# Motor-X.net
KiCad netlist of a schematic drawn in Altium Designer
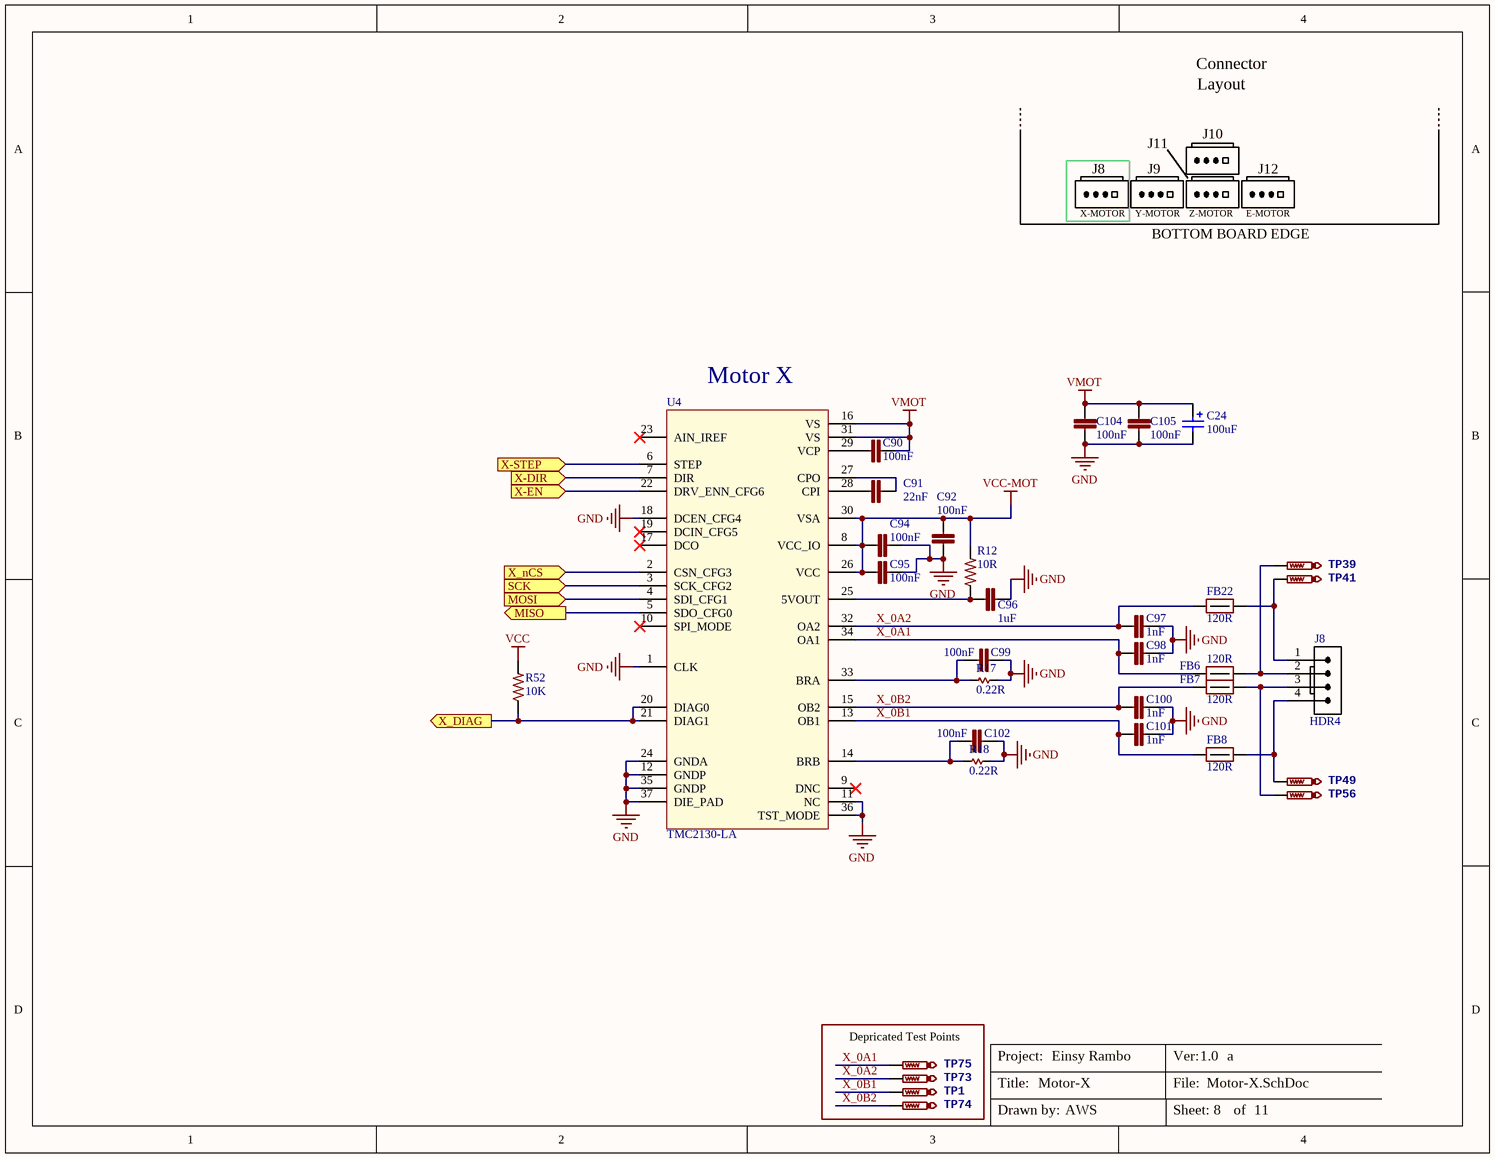
[diagram p0: Motor-X.SchDoc]

(export (version "E")
  (design (tool "Eeschema 10.0.6"))
  (components
    (comp (ref "C24")
      (value "100uF")
      (footprint "CAP-ELEC-063063077")
      (description "CAP ALUM 100UF 35V 20% SMD")
      (fields (field (name "MANUFACTURER") "Nichicon") (field (name "TOLERANCE") "+/- 20%"))
      (libsource (lib "3Delight") (part "UWT1V101MCL1GS"))
    )
    (comp (ref "C90")
      (value "100nF")
      (footprint "C0603")
      (description "CAP CER 0603 100nF 50V 10% X7R")
      (fields (field (name "MANUFACTURER") "Kemet") (field (name "TOLERANCE") "+/- 10%"))
      (libsource (lib "") (part "C0603C104K5RACTU_2"))
    )
    (comp (ref "C91")
      (value "22nF")
      (footprint "C0402")
      (description "CAP CER 0402 22nF ±10% 50V X7R")
      (fields (field (name "MANUFACTURER") "YAGEO") (field (name "TOLERANCE") "+/- 10%"))
      (libsource (lib "3Delight") (part "GCM155R71H223KA55D"))
    )
    (comp (ref "C92")
      (value "100nF")
      (footprint "C0402")
      (description "CAP CER 0402 100nF 16V 10% X7R")
      (fields (field (name "MANUFACTURER") "Murata") (field (name "TOLERANCE") "+/- 10%"))
      (libsource (lib "") (part "GRM155R71C104KA88D_1"))
    )
    (comp (ref "C94")
      (value "100nF")
      (footprint "C0402")
      (description "CAP CER 0402 100nF 16V 10% X7R")
      (fields (field (name "MANUFACTURER") "Murata") (field (name "TOLERANCE") "+/- 10%"))
      (libsource (lib "3Delight") (part "GRM155R71C104KA88D"))
    )
    (comp (ref "C95")
      (value "100nF")
      (footprint "C0402")
      (description "CAP CER 0402 100nF 16V 10% X7R")
      (fields (field (name "MANUFACTURER") "Murata") (field (name "TOLERANCE") "+/- 10%"))
      (libsource (lib "3Delight") (part "GRM155R71C104KA88D"))
    )
    (comp (ref "C96")
      (value "1uF")
      (footprint "C0402")
      (description "CAP CER 0402 1uF 6.3V 10% X5R")
      (fields (field (name "MANUFACTURER") "Murata") (field (name "TOLERANCE") "+/- 10%"))
      (libsource (lib "3Delight") (part "GRM155R60J105KE19D"))
    )
    (comp (ref "C97")
      (value "1nF")
      (footprint "C0603")
      (description "CAP CER 0603  1nF 50v 10% X7R")
      (fields (field (name "MANUFACTURER") "Kemet") (field (name "TOLERANCE") "+/- 10%"))
      (libsource (lib "3Delight") (part "C0603C102K5RACTU"))
    )
    (comp (ref "C98")
      (value "1nF")
      (footprint "C0603")
      (description "CAP CER 0603  1nF 50v 10% X7R")
      (fields (field (name "MANUFACTURER") "Kemet") (field (name "TOLERANCE") "+/- 10%"))
      (libsource (lib "3Delight") (part "C0603C102K5RACTU"))
    )
    (comp (ref "C99")
      (value "100nF")
      (footprint "C0603")
      (description "CAP CER 0603 100nF 50V 10% X7R")
      (fields (field (name "MANUFACTURER") "Kemet") (field (name "TOLERANCE") "+/- 10%"))
      (libsource (lib "") (part "C0603C104K5RACTU_1"))
    )
    (comp (ref "C100")
      (value "1nF")
      (footprint "C0603")
      (description "CAP CER 0603  1nF 50v 10% X7R")
      (fields (field (name "MANUFACTURER") "Kemet") (field (name "TOLERANCE") "+/- 10%"))
      (libsource (lib "3Delight") (part "C0603C102K5RACTU"))
    )
    (comp (ref "C101")
      (value "1nF")
      (footprint "C0603")
      (description "CAP CER 0603  1nF 50v 10% X7R")
      (fields (field (name "MANUFACTURER") "Kemet") (field (name "TOLERANCE") "+/- 10%"))
      (libsource (lib "3Delight") (part "C0603C102K5RACTU"))
    )
    (comp (ref "C102")
      (value "100nF")
      (footprint "C0603")
      (description "CAP CER 0603 100nF 50V 10% X7R")
      (fields (field (name "MANUFACTURER") "Kemet") (field (name "TOLERANCE") "+/- 10%"))
      (libsource (lib "") (part "C0603C104K5RACTU_1"))
    )
    (comp (ref "C104")
      (value "100nF")
      (footprint "C0603")
      (description "CAP CER 0603 100nF 50V 10% X7R")
      (fields (field (name "MANUFACTURER") "Kemet") (field (name "TOLERANCE") "+/- 10%"))
      (libsource (lib "3Delight") (part "C0603C104K5RACTU"))
    )
    (comp (ref "C105")
      (value "100nF")
      (footprint "C0603")
      (description "CAP CER 0603 100nF 50V 10% X7R")
      (fields (field (name "MANUFACTURER") "Kemet") (field (name "TOLERANCE") "+/- 10%"))
      (libsource (lib "3Delight") (part "C0603C104K5RACTU"))
    )
    (comp (ref "FB6")
      (value "120R")
      (footprint "FB0603")
      (description "FERRITE BEAD 120 OHM 0603 1LN")
      (fields (field (name "MANUFACTURER") "Samsung") (field (name "PART") "FERRITE 120R 3A 0603"))
      (libsource (lib "Inductors") (part "FERRITE 120R 3A 0603"))
    )
    (comp (ref "FB7")
      (value "120R")
      (footprint "FB0603")
      (description "FERRITE BEAD 120 OHM 0603 1LN")
      (fields (field (name "MANUFACTURER") "Samsung") (field (name "PART") "FERRITE 120R 3A 0603"))
      (libsource (lib "Inductors") (part "FERRITE 120R 3A 0603"))
    )
    (comp (ref "FB8")
      (value "120R")
      (footprint "FB0603")
      (description "FERRITE BEAD 120 OHM 0603 1LN")
      (fields (field (name "MANUFACTURER") "Samsung") (field (name "PART") "FERRITE 120R 3A 0603"))
      (libsource (lib "Inductors") (part "FERRITE 120R 3A 0603"))
    )
    (comp (ref "FB22")
      (value "120R")
      (footprint "FB0603")
      (description "FERRITE BEAD 120 OHM 0603 1LN")
      (fields (field (name "MANUFACTURER") "Samsung") (field (name "PART") "FERRITE 120R 3A 0603"))
      (libsource (lib "Inductors") (part "FERRITE 120R 3A 0603"))
    )
    (comp (ref "J8")
      (value "HDR4")
      (footprint "4POL254")
      (description "Molex 4 Pin Clip Connector")
      (fields (field (name "MANUFACTURER") "Molex") (field (name "PART") "4 Pin Conn"))
      (libsource (lib "3Delight") (part "CONN 4PIN 0.1{dblquote} VERT SHRD LOCK ALT"))
    )
    (comp (ref "R12")
      (value "10R")
      (footprint "R0402")
      (description "RES SMD 10 OHM 1% 1/16W 0402")
      (fields (field (name "MANUFACTURER") "Yageo") (field (name "TOLERANCE") "+/- 1%"))
      (libsource (lib "3Delight") (part "RC0402FR-0710RL"))
    )
    (comp (ref "R17")
      (value "0.22R")
      (footprint "R1206")
      (description "RES SMD 0.22 OHM 1% 1/3W 1206")
      (fields (field (name "MANUFACTURER") "Panasonic") (field (name "TOLERANCE") "+/- 1%"))
      (libsource (lib "Resistors") (part "0.22R 1% 1206"))
    )
    (comp (ref "R18")
      (value "0.22R")
      (footprint "R1206")
      (description "RES SMD 0.22 OHM 1% 1/3W 1206")
      (fields (field (name "MANUFACTURER") "Panasonic") (field (name "TOLERANCE") "+/- 1%"))
      (libsource (lib "Resistors") (part "0.22R 1% 1206"))
    )
    (comp (ref "R52")
      (value "10K")
      (footprint "R0402")
      (description "RES SMD 10K OHM 1% 1/16W 0402")
      (fields (field (name "MANUFACTURER") "Yageo") (field (name "PART") "10k 1% 0402"))
      (libsource (lib "3Delight") (part "RC0402FR-0710KP"))
    )
    (comp (ref "TP1")
      (value "TestPoint")
      (footprint "TP1-27")
      (description "Test Point")
      (libsource (lib "3Delight") (part "TestPoint"))
    )
    (comp (ref "TP39")
      (value "TestPoint")
      (footprint "TP1-27")
      (description "Test Point")
      (libsource (lib "3Delight") (part "TestPoint"))
    )
    (comp (ref "TP41")
      (value "TestPoint")
      (footprint "TP1-27")
      (description "Test Point")
      (libsource (lib "3Delight") (part "TestPoint"))
    )
    (comp (ref "TP49")
      (value "TestPoint")
      (footprint "TP1-27")
      (description "Test Point")
      (libsource (lib "3Delight") (part "TestPoint"))
    )
    (comp (ref "TP56")
      (value "TestPoint")
      (footprint "TP1-27")
      (description "Test Point")
      (libsource (lib "3Delight") (part "TestPoint"))
    )
    (comp (ref "TP73")
      (value "TestPoint")
      (footprint "TP1-27")
      (description "Test Point")
      (libsource (lib "3Delight") (part "TestPoint"))
    )
    (comp (ref "TP74")
      (value "TestPoint")
      (footprint "TP1-27")
      (description "Test Point")
      (libsource (lib "3Delight") (part "TestPoint"))
    )
    (comp (ref "TP75")
      (value "TestPoint")
      (footprint "TP1-27")
      (description "Test Point")
      (libsource (lib "3Delight") (part "TestPoint"))
    )
    (comp (ref "U4")
      (value "TMC2130-LA")
      (footprint "QFN36-50P500X600X900_HS-37N")
      (description "IC STEPPER MOTOR DVR SPI 36QFN")
      (fields (field (name "MANUFACTURER") "Trinamic") (field (name "PART") "TMC2130"))
      (libsource (lib "3Delight") (part "TMC2130-LA-T"))
    )
  )
  (nets
    (net (code "1") (name "/MISO") (class "Default")
      (node (ref "U4") (pin "5") (pinfunction "SDO_CFG0_5") (pintype "passive"))
    )
    (net (code "2") (name "/MOSI") (class "Default")
      (node (ref "U4") (pin "4") (pinfunction "SDI_CFG1_4") (pintype "passive"))
    )
    (net (code "3") (name "/SCK") (class "Default")
      (node (ref "U4") (pin "3") (pinfunction "SCK_CFG2_3") (pintype "passive"))
    )
    (net (code "4") (name "/X-DIR") (class "Default")
      (node (ref "U4") (pin "7") (pinfunction "DIR_7") (pintype "passive"))
    )
    (net (code "5") (name "/X-EN") (class "Default")
      (node (ref "U4") (pin "22") (pinfunction "DRV_ENN_CFG6_22") (pintype "passive"))
    )
    (net (code "6") (name "/X-STEP") (class "Default")
      (node (ref "U4") (pin "6") (pinfunction "STEP_6") (pintype "passive"))
    )
    (net (code "7") (name "/X_0A1") (class "Default")
      (node (ref "C98") (pin "1") (pinfunction "1_1") (pintype "passive"))
      (node (ref "FB6") (pin "1") (pinfunction "1_1") (pintype "passive"))
      (node (ref "TP75") (pin "TP") (pinfunction "TP_TP") (pintype "passive"))
      (node (ref "U4") (pin "34") (pinfunction "OA1_34") (pintype "passive"))
    )
    (net (code "8") (name "/X_0A2") (class "Default")
      (node (ref "C97") (pin "1") (pinfunction "1_1") (pintype "passive"))
      (node (ref "FB22") (pin "1") (pinfunction "1_1") (pintype "passive"))
      (node (ref "TP73") (pin "TP") (pinfunction "TP_TP") (pintype "passive"))
      (node (ref "U4") (pin "32") (pinfunction "OA2_32") (pintype "passive"))
    )
    (net (code "9") (name "/X_0B1") (class "Default")
      (node (ref "C101") (pin "1") (pinfunction "1_1") (pintype "passive"))
      (node (ref "FB8") (pin "1") (pinfunction "1_1") (pintype "passive"))
      (node (ref "TP1") (pin "TP") (pinfunction "TP_TP") (pintype "passive"))
      (node (ref "U4") (pin "13") (pinfunction "OB1_13") (pintype "passive"))
    )
    (net (code "10") (name "/X_0B2") (class "Default")
      (node (ref "C100") (pin "1") (pinfunction "1_1") (pintype "passive"))
      (node (ref "FB7") (pin "1") (pinfunction "1_1") (pintype "passive"))
      (node (ref "TP74") (pin "TP") (pinfunction "TP_TP") (pintype "passive"))
      (node (ref "U4") (pin "15") (pinfunction "OB2_15") (pintype "passive"))
    )
    (net (code "11") (name "/X_DIAG") (class "Default")
      (node (ref "R52") (pin "1") (pinfunction "1_1") (pintype "passive"))
      (node (ref "U4") (pin "20") (pinfunction "DIAG0_20") (pintype "passive"))
      (node (ref "U4") (pin "21") (pinfunction "DIAG1_21") (pintype "passive"))
    )
    (net (code "12") (name "/X_nCS") (class "Default")
      (node (ref "U4") (pin "2") (pinfunction "CSN_CFG3_2") (pintype "passive"))
    )
    (net (code "13") (name "GND") (class "Default")
      (node (ref "C100") (pin "2") (pinfunction "2_2") (pintype "passive"))
      (node (ref "C101") (pin "2") (pinfunction "2_2") (pintype "passive"))
      (node (ref "C102") (pin "1") (pinfunction "1_1") (pintype "passive"))
      (node (ref "C104") (pin "1") (pinfunction "1_1") (pintype "passive"))
      (node (ref "C105") (pin "1") (pinfunction "1_1") (pintype "passive"))
      (node (ref "C24") (pin "2") (pinfunction "2_2") (pintype "passive"))
      (node (ref "C92") (pin "1") (pinfunction "1_1") (pintype "passive"))
      (node (ref "C94") (pin "1") (pinfunction "1_1") (pintype "passive"))
      (node (ref "C95") (pin "1") (pinfunction "1_1") (pintype "passive"))
      (node (ref "C96") (pin "2") (pinfunction "2_2") (pintype "passive"))
      (node (ref "C97") (pin "2") (pinfunction "2_2") (pintype "passive"))
      (node (ref "C98") (pin "2") (pinfunction "2_2") (pintype "passive"))
      (node (ref "C99") (pin "1") (pinfunction "1_1") (pintype "passive"))
      (node (ref "R17") (pin "2") (pinfunction "2_2") (pintype "passive"))
      (node (ref "R18") (pin "2") (pinfunction "2_2") (pintype "passive"))
      (node (ref "U4") (pin "1") (pinfunction "CLK_1") (pintype "passive"))
      (node (ref "U4") (pin "11") (pinfunction "NC_11") (pintype "passive"))
      (node (ref "U4") (pin "12") (pinfunction "GNDP_12") (pintype "passive"))
      (node (ref "U4") (pin "18") (pinfunction "DCEN_CFG4_18") (pintype "passive"))
      (node (ref "U4") (pin "24") (pinfunction "GNDA_24") (pintype "passive"))
      (node (ref "U4") (pin "35") (pinfunction "GNDP_35") (pintype "passive"))
      (node (ref "U4") (pin "36") (pinfunction "TST_MODE_36") (pintype "passive"))
      (node (ref "U4") (pin "37") (pinfunction "DIE_PAD_37") (pintype "passive"))
    )
    (net (code "14") (name "Net-(FB6-Pad2)") (class "Default")
      (node (ref "FB6") (pin "2") (pinfunction "2_2") (pintype "passive"))
      (node (ref "J8") (pin "2") (pinfunction "2_2") (pintype "passive"))
      (node (ref "TP39") (pin "TP") (pinfunction "TP_TP") (pintype "passive"))
    )
    (net (code "15") (name "Net-(FB7-Pad2)") (class "Default")
      (node (ref "FB7") (pin "2") (pinfunction "2_2") (pintype "passive"))
      (node (ref "J8") (pin "3") (pinfunction "3_3") (pintype "passive"))
      (node (ref "TP56") (pin "TP") (pinfunction "TP_TP") (pintype "passive"))
    )
    (net (code "16") (name "Net-(FB8-Pad2)") (class "Default")
      (node (ref "FB8") (pin "2") (pinfunction "2_2") (pintype "passive"))
      (node (ref "J8") (pin "4") (pinfunction "4_4") (pintype "passive"))
      (node (ref "TP49") (pin "TP") (pinfunction "TP_TP") (pintype "passive"))
    )
    (net (code "17") (name "Net-(FB22-Pad2)") (class "Default")
      (node (ref "FB22") (pin "2") (pinfunction "2_2") (pintype "passive"))
      (node (ref "J8") (pin "1") (pinfunction "1_1") (pintype "passive"))
      (node (ref "TP41") (pin "TP") (pinfunction "TP_TP") (pintype "passive"))
    )
    (net (code "18") (name "Net-(U4-5VOUT)") (class "Default")
      (node (ref "C96") (pin "1") (pinfunction "1_1") (pintype "passive"))
      (node (ref "R12") (pin "1") (pinfunction "1_1") (pintype "passive"))
      (node (ref "U4") (pin "25") (pinfunction "5VOUT_25") (pintype "passive"))
    )
    (net (code "19") (name "Net-(U4-BRA)") (class "Default")
      (node (ref "C99") (pin "2") (pinfunction "2_2") (pintype "passive"))
      (node (ref "R17") (pin "1") (pinfunction "1_1") (pintype "passive"))
      (node (ref "U4") (pin "33") (pinfunction "BRA_33") (pintype "passive"))
    )
    (net (code "20") (name "Net-(U4-BRB)") (class "Default")
      (node (ref "C102") (pin "2") (pinfunction "2_2") (pintype "passive"))
      (node (ref "R18") (pin "1") (pinfunction "1_1") (pintype "passive"))
      (node (ref "U4") (pin "14") (pinfunction "BRB_14") (pintype "passive"))
    )
    (net (code "21") (name "Net-(U4-CPI)") (class "Default")
      (node (ref "C91") (pin "1") (pinfunction "1_1") (pintype "passive"))
      (node (ref "U4") (pin "28") (pinfunction "CPI_28") (pintype "passive"))
    )
    (net (code "22") (name "Net-(U4-CPO)") (class "Default")
      (node (ref "C91") (pin "2") (pinfunction "2_2") (pintype "passive"))
      (node (ref "U4") (pin "27") (pinfunction "CPO_27") (pintype "passive"))
    )
    (net (code "23") (name "Net-(U4-VCP)") (class "Default")
      (node (ref "C90") (pin "1") (pinfunction "1_1") (pintype "passive"))
      (node (ref "U4") (pin "29") (pinfunction "VCP_29") (pintype "passive"))
    )
    (net (code "24") (name "VCC") (class "Default")
      (node (ref "R52") (pin "2") (pinfunction "2_2") (pintype "passive"))
    )
    (net (code "25") (name "VCC-MOT") (class "Default")
      (node (ref "C92") (pin "2") (pinfunction "2_2") (pintype "passive"))
      (node (ref "C94") (pin "2") (pinfunction "2_2") (pintype "passive"))
      (node (ref "C95") (pin "2") (pinfunction "2_2") (pintype "passive"))
      (node (ref "R12") (pin "2") (pinfunction "2_2") (pintype "passive"))
      (node (ref "U4") (pin "26") (pinfunction "VCC_26") (pintype "passive"))
      (node (ref "U4") (pin "30") (pinfunction "VSA_30") (pintype "passive"))
      (node (ref "U4") (pin "8") (pinfunction "VCC_IO_8") (pintype "passive"))
    )
    (net (code "26") (name "VMOT") (class "Default")
      (node (ref "C104") (pin "2") (pinfunction "2_2") (pintype "passive"))
      (node (ref "C105") (pin "2") (pinfunction "2_2") (pintype "passive"))
      (node (ref "C24") (pin "1") (pinfunction "1_1") (pintype "passive"))
      (node (ref "C90") (pin "2") (pinfunction "2_2") (pintype "passive"))
      (node (ref "U4") (pin "16") (pinfunction "VS_16") (pintype "passive"))
      (node (ref "U4") (pin "31") (pinfunction "VS_31") (pintype "passive"))
    )
    (net (code "27") (name "unconnected-(U4-AIN_IREF-Pad23)") (class "Default")
      (node (ref "U4") (pin "23") (pinfunction "AIN_IREF_23") (pintype "passive+no_connect"))
    )
    (net (code "28") (name "unconnected-(U4-DCIN_CFG5-Pad19)") (class "Default")
      (node (ref "U4") (pin "19") (pinfunction "DCIN_CFG5_19") (pintype "passive+no_connect"))
    )
    (net (code "29") (name "unconnected-(U4-DCO-Pad17)") (class "Default")
      (node (ref "U4") (pin "17") (pinfunction "DCO_17") (pintype "passive+no_connect"))
    )
    (net (code "30") (name "unconnected-(U4-DNC-Pad9)") (class "Default")
      (node (ref "U4") (pin "9") (pinfunction "DNC_9") (pintype "passive+no_connect"))
    )
    (net (code "31") (name "unconnected-(U4-SPI_MODE-Pad10)") (class "Default")
      (node (ref "U4") (pin "10") (pinfunction "SPI_MODE_10") (pintype "passive+no_connect"))
    )
  )
)
